# Vending_Machine.net
KiCad netlist of a schematic drawn in EAGLE
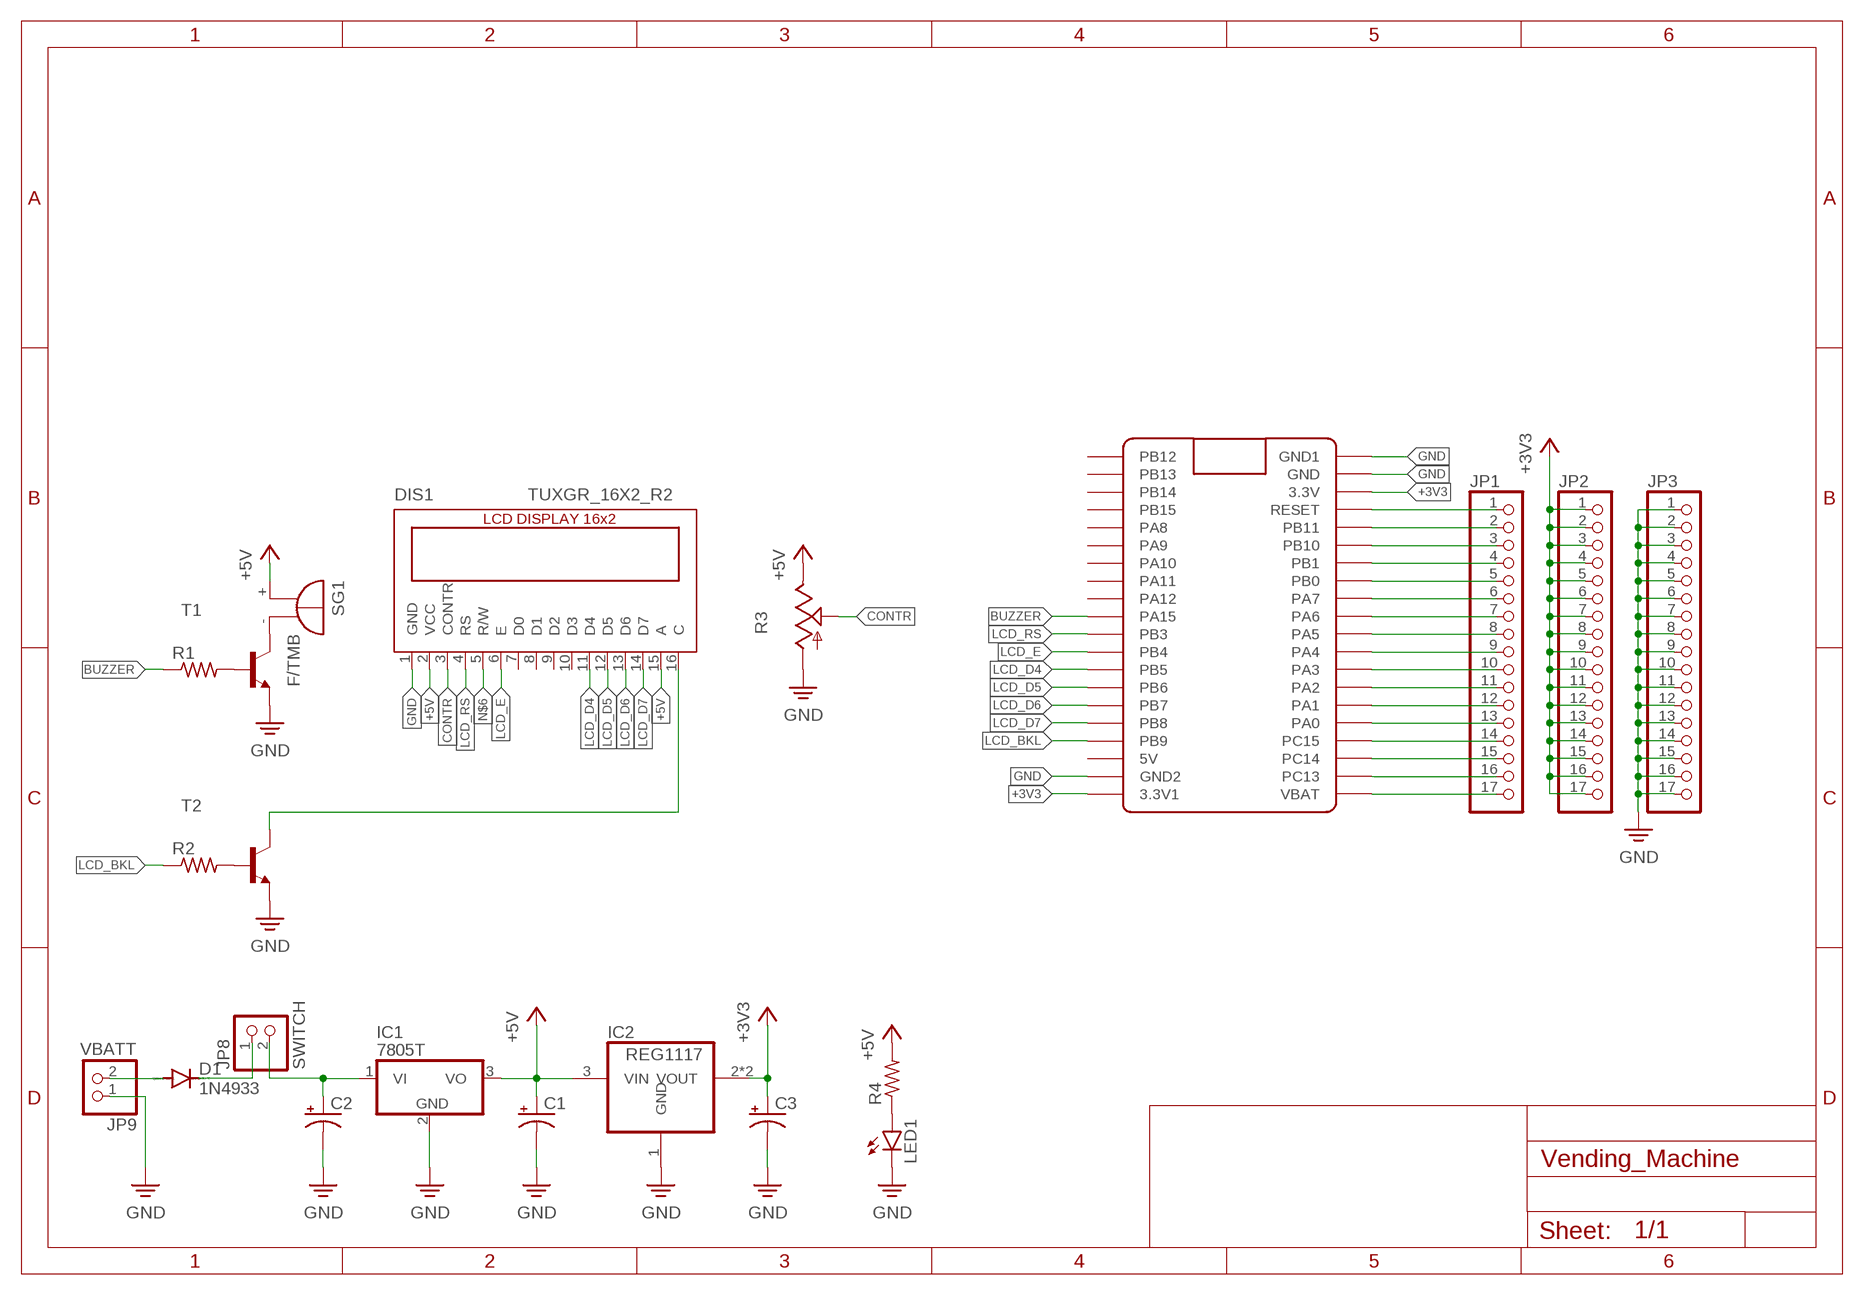
[diagram p0: schematic, sheet 1]

(export (version "E")
  (design (tool "Eeschema 10.0.6"))
  (components
    (comp (ref "C1")
      (value "CPOL-USE2.5-6")
      (footprint "eagle-import:E2,5-6")
      (libsource (lib "eagle-import") (part "CPOL-USE2.5-6"))
    )
    (comp (ref "C2")
      (value "CPOL-USE2.5-6")
      (footprint "eagle-import:E2,5-6")
      (libsource (lib "eagle-import") (part "CPOL-USE2.5-6"))
    )
    (comp (ref "C3")
      (value "CPOL-USE2.5-6")
      (footprint "eagle-import:E2,5-6")
      (libsource (lib "eagle-import") (part "CPOL-USE2.5-6"))
    )
    (comp (ref "D1")
      (value "1N4933")
      (footprint "eagle-import:DO41-10")
      (libsource (lib "eagle-import") (part "1N4933"))
    )
    (comp (ref "DIS1")
      (value "TUXGR_16X2_R2")
      (footprint "eagle-import:TUXGR_16X2_R2")
      (libsource (lib "eagle-import") (part "TUXGR_16X2_R2"))
    )
    (comp (ref "IC1")
      (value "7805T")
      (footprint "eagle-import:TO220H")
      (libsource (lib "eagle-import") (part "78T05"))
    )
    (comp (ref "IC2")
      (value "REG1117")
      (footprint "eagle-import:SOT223")
      (libsource (lib "eagle-import") (part "REG1117"))
    )
    (comp (ref "JP1")
      (value "PINHD-1X17")
      (footprint "eagle-import:1X17")
      (libsource (lib "eagle-import") (part "PINHD-1X17"))
    )
    (comp (ref "JP2")
      (value "PINHD-1X17")
      (footprint "eagle-import:1X17")
      (libsource (lib "eagle-import") (part "PINHD-1X17"))
    )
    (comp (ref "JP3")
      (value "PINHD-1X17")
      (footprint "eagle-import:1X17")
      (libsource (lib "eagle-import") (part "PINHD-1X17"))
    )
    (comp (ref "JP8")
      (value "SWITCH")
      (footprint "eagle-import:1X02")
      (libsource (lib "eagle-import") (part "PINHD-1X2"))
    )
    (comp (ref "JP9")
      (value "VBATT")
      (footprint "eagle-import:1X02")
      (libsource (lib "eagle-import") (part "PINHD-1X2"))
    )
    (comp (ref "LED1")
      (value "LED3MM")
      (footprint "eagle-import:LED3MM")
      (libsource (lib "eagle-import") (part "LED3MM"))
    )
    (comp (ref "R1")
      (value "R-US_0204/7")
      (footprint "eagle-import:0204_7")
      (libsource (lib "eagle-import") (part "R-US_0204/7"))
    )
    (comp (ref "R2")
      (value "R-US_0204/7")
      (footprint "eagle-import:0204_7")
      (libsource (lib "eagle-import") (part "R-US_0204/7"))
    )
    (comp (ref "R3")
      (value "TRIM_US-CA6V")
      (footprint "eagle-import:CA6V")
      (libsource (lib "eagle-import") (part "TRIM_US-CA6V"))
    )
    (comp (ref "R4")
      (value "R-US_0204/7")
      (footprint "eagle-import:0204_7")
      (libsource (lib "eagle-import") (part "R-US_0204/7"))
    )
    (comp (ref "SG1")
      (value "F/TMB")
      (footprint "eagle-import:F_TMB")
      (libsource (lib "eagle-import") (part "F/TMB"))
    )
    (comp (ref "T1")
      (value "BC167-NPN-TO92-ECB")
      (footprint "eagle-import:TO92-ECB")
      (libsource (lib "eagle-import") (part "-NPN-TO92-ECBBC167"))
    )
    (comp (ref "T2")
      (value "BC167-NPN-TO92-ECB")
      (footprint "eagle-import:TO92-ECB")
      (libsource (lib "eagle-import") (part "-NPN-TO92-ECBBC167"))
    )
    (comp (ref "U$1")
      (value "BLUE_PILL")
      (footprint "eagle-import:BLUE_PILL")
      (libsource (lib "eagle-import") (part "BLUE_PILL"))
    )
  )
  (nets
    (net (code "1") (name "+3V3") (class "Default")
      (node (ref "C3") (pin "+") (pinfunction "+_+") (pintype "passive"))
      (node (ref "IC2") (pin "2") (pinfunction "VOUT_2") (pintype "output"))
      (node (ref "IC2") (pin "4") (pinfunction "VOUT_4") (pintype "output"))
      (node (ref "JP2") (pin "1") (pinfunction "1_1") (pintype "passive"))
      (node (ref "JP2") (pin "10") (pinfunction "10_10") (pintype "passive"))
      (node (ref "JP2") (pin "11") (pinfunction "11_11") (pintype "passive"))
      (node (ref "JP2") (pin "12") (pinfunction "12_12") (pintype "passive"))
      (node (ref "JP2") (pin "13") (pinfunction "13_13") (pintype "passive"))
      (node (ref "JP2") (pin "14") (pinfunction "14_14") (pintype "passive"))
      (node (ref "JP2") (pin "15") (pinfunction "15_15") (pintype "passive"))
      (node (ref "JP2") (pin "16") (pinfunction "16_16") (pintype "passive"))
      (node (ref "JP2") (pin "17") (pinfunction "17_17") (pintype "passive"))
      (node (ref "JP2") (pin "2") (pinfunction "2_2") (pintype "passive"))
      (node (ref "JP2") (pin "3") (pinfunction "3_3") (pintype "passive"))
      (node (ref "JP2") (pin "4") (pinfunction "4_4") (pintype "passive"))
      (node (ref "JP2") (pin "5") (pinfunction "5_5") (pintype "passive"))
      (node (ref "JP2") (pin "6") (pinfunction "6_6") (pintype "passive"))
      (node (ref "JP2") (pin "7") (pinfunction "7_7") (pintype "passive"))
      (node (ref "JP2") (pin "8") (pinfunction "8_8") (pintype "passive"))
      (node (ref "JP2") (pin "9") (pinfunction "9_9") (pintype "passive"))
      (node (ref "U$1") (pin "P$20") (pinfunction "3.3V1_P$20") (pintype "bidirectional"))
      (node (ref "U$1") (pin "P$23") (pinfunction "3.3V_P$23") (pintype "bidirectional"))
    )
    (net (code "2") (name "+5V") (class "Default")
      (node (ref "C1") (pin "+") (pinfunction "+_+") (pintype "passive"))
      (node (ref "DIS1") (pin "15") (pinfunction "A_15") (pintype "input"))
      (node (ref "DIS1") (pin "2") (pinfunction "VCC_2") (pintype "power_in"))
      (node (ref "IC1") (pin "3") (pinfunction "VO_3") (pintype "passive"))
      (node (ref "IC2") (pin "3") (pinfunction "VIN_3") (pintype "input"))
      (node (ref "R3") (pin "E") (pinfunction "E_E") (pintype "passive"))
      (node (ref "R4") (pin "2") (pinfunction "2_2") (pintype "passive"))
      (node (ref "SG1") (pin "+") (pinfunction "+_+") (pintype "passive"))
    )
    (net (code "3") (name "BUZZER") (class "Default")
      (node (ref "R1") (pin "1") (pinfunction "1_1") (pintype "passive"))
      (node (ref "U$1") (pin "P$10") (pinfunction "PA15_P$10") (pintype "bidirectional"))
    )
    (net (code "4") (name "CONTR") (class "Default")
      (node (ref "DIS1") (pin "3") (pinfunction "CONTR_3") (pintype "input"))
      (node (ref "R3") (pin "S") (pinfunction "S_S") (pintype "passive"))
    )
    (net (code "5") (name "GND") (class "Default")
      (node (ref "C1") (pin "-") (pinfunction "-_-") (pintype "passive"))
      (node (ref "C2") (pin "-") (pinfunction "-_-") (pintype "passive"))
      (node (ref "C3") (pin "-") (pinfunction "-_-") (pintype "passive"))
      (node (ref "DIS1") (pin "1") (pinfunction "GND_1") (pintype "power_in"))
      (node (ref "IC1") (pin "2") (pinfunction "GND_2") (pintype "passive"))
      (node (ref "IC2") (pin "1") (pinfunction "GND_1") (pintype "power_in"))
      (node (ref "JP3") (pin "1") (pinfunction "1_1") (pintype "passive"))
      (node (ref "JP3") (pin "10") (pinfunction "10_10") (pintype "passive"))
      (node (ref "JP3") (pin "11") (pinfunction "11_11") (pintype "passive"))
      (node (ref "JP3") (pin "12") (pinfunction "12_12") (pintype "passive"))
      (node (ref "JP3") (pin "13") (pinfunction "13_13") (pintype "passive"))
      (node (ref "JP3") (pin "14") (pinfunction "14_14") (pintype "passive"))
      (node (ref "JP3") (pin "15") (pinfunction "15_15") (pintype "passive"))
      (node (ref "JP3") (pin "16") (pinfunction "16_16") (pintype "passive"))
      (node (ref "JP3") (pin "17") (pinfunction "17_17") (pintype "passive"))
      (node (ref "JP3") (pin "2") (pinfunction "2_2") (pintype "passive"))
      (node (ref "JP3") (pin "3") (pinfunction "3_3") (pintype "passive"))
      (node (ref "JP3") (pin "4") (pinfunction "4_4") (pintype "passive"))
      (node (ref "JP3") (pin "5") (pinfunction "5_5") (pintype "passive"))
      (node (ref "JP3") (pin "6") (pinfunction "6_6") (pintype "passive"))
      (node (ref "JP3") (pin "7") (pinfunction "7_7") (pintype "passive"))
      (node (ref "JP3") (pin "8") (pinfunction "8_8") (pintype "passive"))
      (node (ref "JP3") (pin "9") (pinfunction "9_9") (pintype "passive"))
      (node (ref "JP9") (pin "1") (pinfunction "1_1") (pintype "passive"))
      (node (ref "LED1") (pin "K") (pinfunction "C_K") (pintype "passive"))
      (node (ref "R3") (pin "A") (pinfunction "A_A") (pintype "passive"))
      (node (ref "T1") (pin "E") (pinfunction "E_E") (pintype "passive"))
      (node (ref "T2") (pin "E") (pinfunction "E_E") (pintype "passive"))
      (node (ref "U$1") (pin "P$19") (pinfunction "GND2_P$19") (pintype "bidirectional"))
      (node (ref "U$1") (pin "P$21") (pinfunction "GND1_P$21") (pintype "power_in"))
      (node (ref "U$1") (pin "P$22") (pinfunction "GND_P$22") (pintype "bidirectional"))
    )
    (net (code "6") (name "LCD_BKL") (class "Default")
      (node (ref "R2") (pin "1") (pinfunction "1_1") (pintype "passive"))
      (node (ref "U$1") (pin "P$17") (pinfunction "PB9_P$17") (pintype "bidirectional"))
    )
    (net (code "7") (name "LCD_D4") (class "Default")
      (node (ref "DIS1") (pin "11") (pinfunction "D4_11") (pintype "input"))
      (node (ref "U$1") (pin "P$13") (pinfunction "PB5_P$13") (pintype "bidirectional"))
    )
    (net (code "8") (name "LCD_D5") (class "Default")
      (node (ref "DIS1") (pin "12") (pinfunction "D5_12") (pintype "input"))
      (node (ref "U$1") (pin "P$14") (pinfunction "PB6_P$14") (pintype "bidirectional"))
    )
    (net (code "9") (name "LCD_D6") (class "Default")
      (node (ref "DIS1") (pin "13") (pinfunction "D6_13") (pintype "input"))
      (node (ref "U$1") (pin "P$15") (pinfunction "PB7_P$15") (pintype "bidirectional"))
    )
    (net (code "10") (name "LCD_D7") (class "Default")
      (node (ref "DIS1") (pin "14") (pinfunction "D7_14") (pintype "input"))
      (node (ref "U$1") (pin "P$16") (pinfunction "PB8_P$16") (pintype "bidirectional"))
    )
    (net (code "11") (name "LCD_E") (class "Default")
      (node (ref "DIS1") (pin "6") (pinfunction "E_6") (pintype "input"))
      (node (ref "U$1") (pin "P$12") (pinfunction "PB4_P$12") (pintype "bidirectional"))
    )
    (net (code "12") (name "LCD_RS") (class "Default")
      (node (ref "DIS1") (pin "4") (pinfunction "RS_4") (pintype "input"))
      (node (ref "U$1") (pin "P$11") (pinfunction "PB3_P$11") (pintype "bidirectional"))
    )
    (net (code "13") (name "N$6") (class "Default")
      (node (ref "DIS1") (pin "5") (pinfunction "R/W_5") (pintype "input"))
    )
    (net (code "14") (name "Net-(D1-PadA)") (class "Default")
      (node (ref "D1") (pin "A") (pinfunction "A_A") (pintype "passive"))
      (node (ref "JP9") (pin "2") (pinfunction "2_2") (pintype "passive"))
    )
    (net (code "15") (name "Net-(D1-PadC)") (class "Default")
      (node (ref "D1") (pin "C") (pinfunction "C_C") (pintype "passive"))
      (node (ref "JP8") (pin "1") (pinfunction "1_1") (pintype "passive"))
    )
    (net (code "16") (name "Net-(DIS1-C)") (class "Default")
      (node (ref "DIS1") (pin "16") (pinfunction "C_16") (pintype "input"))
      (node (ref "T2") (pin "C") (pinfunction "C_C") (pintype "passive"))
    )
    (net (code "17") (name "Net-(IC1-VI)") (class "Default")
      (node (ref "C2") (pin "+") (pinfunction "+_+") (pintype "passive"))
      (node (ref "IC1") (pin "1") (pinfunction "VI_1") (pintype "input"))
      (node (ref "JP8") (pin "2") (pinfunction "2_2") (pintype "passive"))
    )
    (net (code "18") (name "Net-(LED1-PadA)") (class "Default")
      (node (ref "LED1") (pin "A") (pinfunction "A_A") (pintype "passive"))
      (node (ref "R4") (pin "1") (pinfunction "1_1") (pintype "passive"))
    )
    (net (code "19") (name "Net-(R1-Pad2)") (class "Default")
      (node (ref "R1") (pin "2") (pinfunction "2_2") (pintype "passive"))
      (node (ref "T1") (pin "B") (pinfunction "B_B") (pintype "passive"))
    )
    (net (code "20") (name "Net-(R2-Pad2)") (class "Default")
      (node (ref "R2") (pin "2") (pinfunction "2_2") (pintype "passive"))
      (node (ref "T2") (pin "B") (pinfunction "B_B") (pintype "passive"))
    )
    (net (code "21") (name "Net-(SG1-Pad-)") (class "Default")
      (node (ref "SG1") (pin "-") (pinfunction "-_-") (pintype "passive"))
      (node (ref "T1") (pin "C") (pinfunction "C_C") (pintype "passive"))
    )
    (net (code "22") (name "Net-(U$1-PA0)") (class "Default")
      (node (ref "JP1") (pin "13") (pinfunction "13_13") (pintype "passive"))
      (node (ref "U$1") (pin "P$36") (pinfunction "PA0_P$36") (pintype "bidirectional"))
    )
    (net (code "23") (name "Net-(U$1-PA1)") (class "Default")
      (node (ref "JP1") (pin "12") (pinfunction "12_12") (pintype "passive"))
      (node (ref "U$1") (pin "P$35") (pinfunction "PA1_P$35") (pintype "bidirectional"))
    )
    (net (code "24") (name "Net-(U$1-PA2)") (class "Default")
      (node (ref "JP1") (pin "11") (pinfunction "11_11") (pintype "passive"))
      (node (ref "U$1") (pin "P$34") (pinfunction "PA2_P$34") (pintype "bidirectional"))
    )
    (net (code "25") (name "Net-(U$1-PA3)") (class "Default")
      (node (ref "JP1") (pin "10") (pinfunction "10_10") (pintype "passive"))
      (node (ref "U$1") (pin "P$33") (pinfunction "PA3_P$33") (pintype "bidirectional"))
    )
    (net (code "26") (name "Net-(U$1-PA4)") (class "Default")
      (node (ref "JP1") (pin "9") (pinfunction "9_9") (pintype "passive"))
      (node (ref "U$1") (pin "P$32") (pinfunction "PA4_P$32") (pintype "bidirectional"))
    )
    (net (code "27") (name "Net-(U$1-PA5)") (class "Default")
      (node (ref "JP1") (pin "8") (pinfunction "8_8") (pintype "passive"))
      (node (ref "U$1") (pin "P$31") (pinfunction "PA5_P$31") (pintype "bidirectional"))
    )
    (net (code "28") (name "Net-(U$1-PA6)") (class "Default")
      (node (ref "JP1") (pin "7") (pinfunction "7_7") (pintype "passive"))
      (node (ref "U$1") (pin "P$30") (pinfunction "PA6_P$30") (pintype "bidirectional"))
    )
    (net (code "29") (name "Net-(U$1-PA7)") (class "Default")
      (node (ref "JP1") (pin "6") (pinfunction "6_6") (pintype "passive"))
      (node (ref "U$1") (pin "P$29") (pinfunction "PA7_P$29") (pintype "bidirectional"))
    )
    (net (code "30") (name "Net-(U$1-PB0)") (class "Default")
      (node (ref "JP1") (pin "5") (pinfunction "5_5") (pintype "passive"))
      (node (ref "U$1") (pin "P$28") (pinfunction "PB0_P$28") (pintype "bidirectional"))
    )
    (net (code "31") (name "Net-(U$1-PB1)") (class "Default")
      (node (ref "JP1") (pin "4") (pinfunction "4_4") (pintype "passive"))
      (node (ref "U$1") (pin "P$27") (pinfunction "PB1_P$27") (pintype "bidirectional"))
    )
    (net (code "32") (name "Net-(U$1-PB10)") (class "Default")
      (node (ref "JP1") (pin "3") (pinfunction "3_3") (pintype "passive"))
      (node (ref "U$1") (pin "P$26") (pinfunction "PB10_P$26") (pintype "bidirectional"))
    )
    (net (code "33") (name "Net-(U$1-PB11)") (class "Default")
      (node (ref "JP1") (pin "2") (pinfunction "2_2") (pintype "passive"))
      (node (ref "U$1") (pin "P$25") (pinfunction "PB11_P$25") (pintype "bidirectional"))
    )
    (net (code "34") (name "Net-(U$1-PC13)") (class "Default")
      (node (ref "JP1") (pin "16") (pinfunction "16_16") (pintype "passive"))
      (node (ref "U$1") (pin "P$39") (pinfunction "PC13_P$39") (pintype "bidirectional"))
    )
    (net (code "35") (name "Net-(U$1-PC14)") (class "Default")
      (node (ref "JP1") (pin "15") (pinfunction "15_15") (pintype "passive"))
      (node (ref "U$1") (pin "P$38") (pinfunction "PC14_P$38") (pintype "bidirectional"))
    )
    (net (code "36") (name "Net-(U$1-PC15)") (class "Default")
      (node (ref "JP1") (pin "14") (pinfunction "14_14") (pintype "passive"))
      (node (ref "U$1") (pin "P$37") (pinfunction "PC15_P$37") (pintype "bidirectional"))
    )
    (net (code "37") (name "Net-(U$1-RESET)") (class "Default")
      (node (ref "JP1") (pin "1") (pinfunction "1_1") (pintype "passive"))
      (node (ref "U$1") (pin "P$24") (pinfunction "RESET_P$24") (pintype "bidirectional"))
    )
    (net (code "38") (name "Net-(U$1-VBAT)") (class "Default")
      (node (ref "JP1") (pin "17") (pinfunction "17_17") (pintype "passive"))
      (node (ref "U$1") (pin "P$40") (pinfunction "VBAT_P$40") (pintype "bidirectional"))
    )
    (net (code "39") (name "unconnected-(DIS1-D0-Pad7)") (class "Default")
      (node (ref "DIS1") (pin "7") (pinfunction "D0_7") (pintype "input"))
    )
    (net (code "40") (name "unconnected-(DIS1-D1-Pad8)") (class "Default")
      (node (ref "DIS1") (pin "8") (pinfunction "D1_8") (pintype "input"))
    )
    (net (code "41") (name "unconnected-(DIS1-D2-Pad9)") (class "Default")
      (node (ref "DIS1") (pin "9") (pinfunction "D2_9") (pintype "input"))
    )
    (net (code "42") (name "unconnected-(DIS1-D3-Pad10)") (class "Default")
      (node (ref "DIS1") (pin "10") (pinfunction "D3_10") (pintype "input"))
    )
    (net (code "43") (name "unconnected-(U$1-5V-PadP$18)") (class "Default")
      (node (ref "U$1") (pin "P$18") (pinfunction "5V_P$18") (pintype "bidirectional"))
    )
    (net (code "44") (name "unconnected-(U$1-PA8-PadP$5)") (class "Default")
      (node (ref "U$1") (pin "P$5") (pinfunction "PA8_P$5") (pintype "bidirectional"))
    )
    (net (code "45") (name "unconnected-(U$1-PA9-PadP$6)") (class "Default")
      (node (ref "U$1") (pin "P$6") (pinfunction "PA9_P$6") (pintype "bidirectional"))
    )
    (net (code "46") (name "unconnected-(U$1-PA10-PadP$7)") (class "Default")
      (node (ref "U$1") (pin "P$7") (pinfunction "PA10_P$7") (pintype "bidirectional"))
    )
    (net (code "47") (name "unconnected-(U$1-PA11-PadP$8)") (class "Default")
      (node (ref "U$1") (pin "P$8") (pinfunction "PA11_P$8") (pintype "bidirectional"))
    )
    (net (code "48") (name "unconnected-(U$1-PA12-PadP$9)") (class "Default")
      (node (ref "U$1") (pin "P$9") (pinfunction "PA12_P$9") (pintype "bidirectional"))
    )
    (net (code "49") (name "unconnected-(U$1-PB12-PadP$1)") (class "Default")
      (node (ref "U$1") (pin "P$1") (pinfunction "PB12_P$1") (pintype "bidirectional"))
    )
    (net (code "50") (name "unconnected-(U$1-PB13-PadP$2)") (class "Default")
      (node (ref "U$1") (pin "P$2") (pinfunction "PB13_P$2") (pintype "bidirectional"))
    )
    (net (code "51") (name "unconnected-(U$1-PB14-PadP$3)") (class "Default")
      (node (ref "U$1") (pin "P$3") (pinfunction "PB14_P$3") (pintype "bidirectional"))
    )
    (net (code "52") (name "unconnected-(U$1-PB15-PadP$4)") (class "Default")
      (node (ref "U$1") (pin "P$4") (pinfunction "PB15_P$4") (pintype "bidirectional"))
    )
  )
)
